# design.net
KiCad netlist of a schematic drawn in Altium Designer
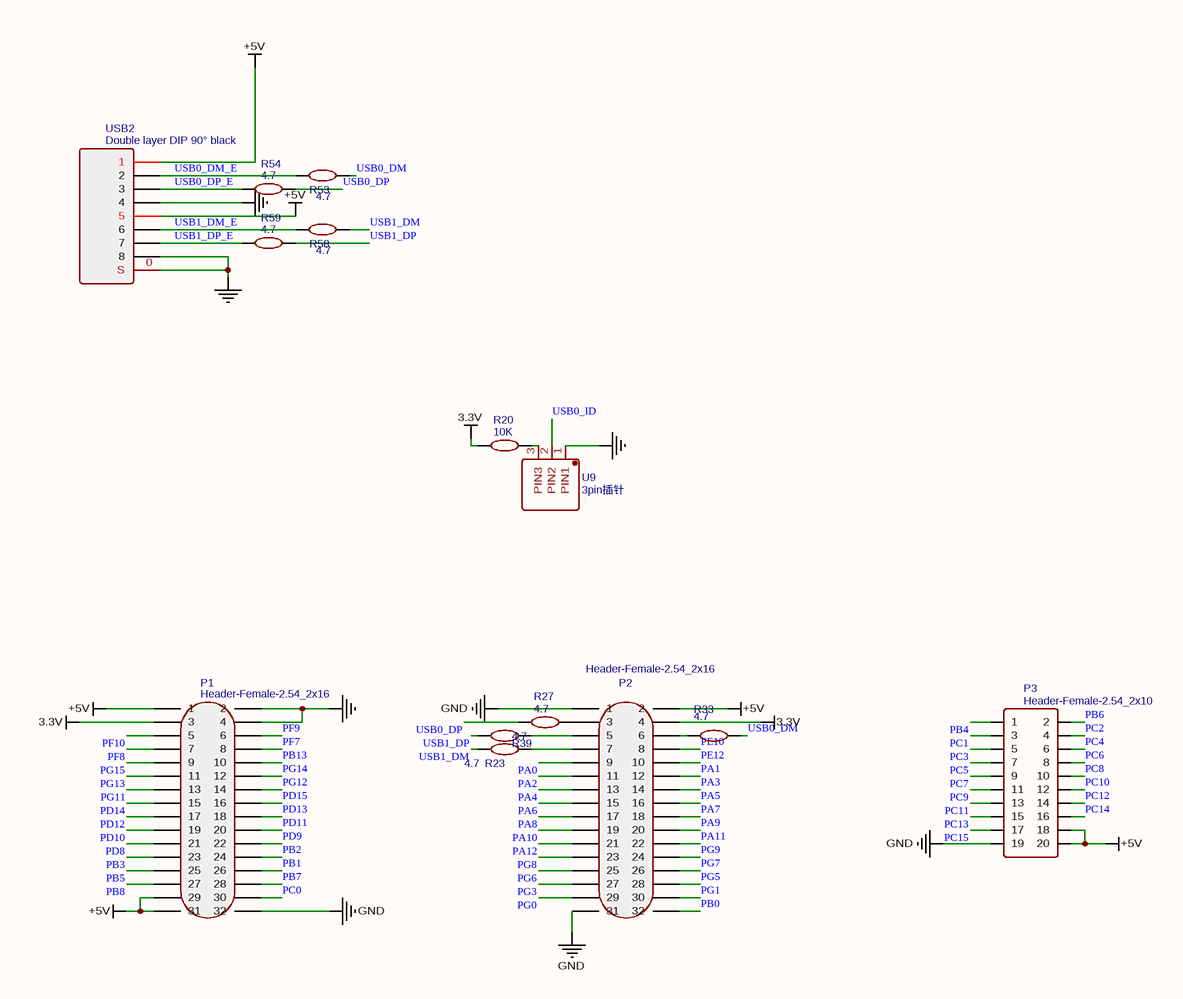
[diagram p0: 接口单元.schdoc]

(export (version "E")
  (design (tool "Eeschema 10.0.6"))
  (components
    (comp (ref "P1")
      (value "Header-Female-2.54_2x16")
      (footprint "HDR-16X2/2.54")
      (fields (field (name "BOM_SUPPLIER PART") "E55795"))
      (libsource (lib "altium-import") (part "root_0_Header-Female-2.54_2x16_"))
    )
    (comp (ref "P2")
      (value "Header-Female-2.54_2x16")
      (footprint "HDR-16X2/2.54")
      (fields (field (name "BOM_SUPPLIER PART") "E55795"))
      (libsource (lib "altium-import") (part "root_0_Header-Female-2.54_2x16_"))
    )
    (comp (ref "P3")
      (value "Header-Female-2.54_2x10")
      (footprint "HDR-10X2/2.54")
      (fields
        (field (name "BOM_MANUFACTURER PART") "2.54mm,2×10Double row female")
        (field (name "BOM_SUPPLIER PART") "C30867")
      )
      (libsource (lib "altium-import") (part "root_0_Header-Female-2.54_2x10_"))
    )
    (comp (ref "R20")
      (value "10K")
      (footprint "0603")
      (fields
        (field (name "BOM_MANUFACTURER PART") "0603WAF1002T5E")
        (field (name "BOM_SUPPLIER PART") "C25804")
      )
      (libsource (lib "altium-import") (part "root_2_10K_"))
    )
    (comp (ref "R23")
      (value "4.7")
      (footprint "0603")
      (fields
        (field (name "BOM_MANUFACTURER PART") "0603WAF470KT5E")
        (field (name "BOM_SUPPLIER PART") "C23164")
      )
      (libsource (lib "altium-import") (part "root_0_4.7_"))
    )
    (comp (ref "R27")
      (value "4.7")
      (footprint "0603")
      (fields
        (field (name "BOM_MANUFACTURER PART") "0603WAF470KT5E")
        (field (name "BOM_SUPPLIER PART") "C23164")
      )
      (libsource (lib "altium-import") (part "root_2_4.7_"))
    )
    (comp (ref "R33")
      (value "4.7")
      (footprint "0603")
      (fields
        (field (name "BOM_MANUFACTURER PART") "0603WAF470KT5E")
        (field (name "BOM_SUPPLIER PART") "C23164")
      )
      (libsource (lib "altium-import") (part "root_0_4.7_"))
    )
    (comp (ref "R39")
      (value "4.7")
      (footprint "0603")
      (fields
        (field (name "BOM_MANUFACTURER PART") "0603WAF470KT5E")
        (field (name "BOM_SUPPLIER PART") "C23164")
      )
      (libsource (lib "altium-import") (part "root_0_4.7_"))
    )
    (comp (ref "R53")
      (value "4.7")
      (footprint "0603")
      (fields
        (field (name "BOM_MANUFACTURER PART") "0603WAF470KT5E")
        (field (name "BOM_SUPPLIER PART") "C23164")
      )
      (libsource (lib "altium-import") (part "root_0_4.7_"))
    )
    (comp (ref "R54")
      (value "4.7")
      (footprint "0603")
      (fields
        (field (name "BOM_MANUFACTURER PART") "0603WAF470KT5E")
        (field (name "BOM_SUPPLIER PART") "C23164")
      )
      (libsource (lib "altium-import") (part "root_0_4.7_"))
    )
    (comp (ref "R58")
      (value "4.7")
      (footprint "0603")
      (fields
        (field (name "BOM_MANUFACTURER PART") "0603WAF470KT5E")
        (field (name "BOM_SUPPLIER PART") "C23164")
      )
      (libsource (lib "altium-import") (part "root_0_4.7_"))
    )
    (comp (ref "R59")
      (value "4.7")
      (footprint "0603")
      (fields
        (field (name "BOM_MANUFACTURER PART") "0603WAF470KT5E")
        (field (name "BOM_SUPPLIER PART") "C23164")
      )
      (libsource (lib "altium-import") (part "root_0_4.7_"))
    )
    (comp (ref "U9")
      (value "3pin插针")
      (footprint "HDR-3X1/2.54")
      (fields (field (name "CONTRIBUTOR") "DesignMyself"))
      (libsource (lib "altium-import") (part "root_3_3pin插针_"))
    )
    (comp (ref "USB2")
      (value "Double layer DIP 90° black")
      (footprint "USB-M-51")
      (fields (field (name "BOM_SUPPLIER PART") "C12049"))
      (libsource (lib "altium-import") (part "root_0_Double layer DIP 90° black_"))
    )
  )
  (nets
    (net (code "1") (name "+5V") (class "Default")
      (node (ref "P1") (pin "1") (pinfunction "1_1") (pintype "passive"))
      (node (ref "P1") (pin "29") (pinfunction "29_29") (pintype "passive"))
      (node (ref "P1") (pin "31") (pinfunction "31_31") (pintype "passive"))
      (node (ref "P2") (pin "2") (pinfunction "2_2") (pintype "passive"))
      (node (ref "P3") (pin "18") (pinfunction "18_18") (pintype "passive"))
      (node (ref "P3") (pin "20") (pinfunction "20_20") (pintype "passive"))
      (node (ref "USB2") (pin "1") (pinfunction "1_1") (pintype "passive"))
      (node (ref "USB2") (pin "5") (pinfunction "5_5") (pintype "passive"))
    )
    (net (code "2") (name "/PA0") (class "Default")
      (node (ref "P2") (pin "9") (pinfunction "9_9") (pintype "passive"))
    )
    (net (code "3") (name "/PA1") (class "Default")
      (node (ref "P2") (pin "12") (pinfunction "12_12") (pintype "passive"))
    )
    (net (code "4") (name "/PA2") (class "Default")
      (node (ref "P2") (pin "11") (pinfunction "11_11") (pintype "passive"))
    )
    (net (code "5") (name "/PA3") (class "Default")
      (node (ref "P2") (pin "14") (pinfunction "14_14") (pintype "passive"))
    )
    (net (code "6") (name "/PA4") (class "Default")
      (node (ref "P2") (pin "13") (pinfunction "13_13") (pintype "passive"))
    )
    (net (code "7") (name "/PA5") (class "Default")
      (node (ref "P2") (pin "16") (pinfunction "16_16") (pintype "passive"))
    )
    (net (code "8") (name "/PA6") (class "Default")
      (node (ref "P2") (pin "15") (pinfunction "15_15") (pintype "passive"))
    )
    (net (code "9") (name "/PA7") (class "Default")
      (node (ref "P2") (pin "18") (pinfunction "18_18") (pintype "passive"))
    )
    (net (code "10") (name "/PA8") (class "Default")
      (node (ref "P2") (pin "17") (pinfunction "17_17") (pintype "passive"))
    )
    (net (code "11") (name "/PA9") (class "Default")
      (node (ref "P2") (pin "20") (pinfunction "20_20") (pintype "passive"))
    )
    (net (code "12") (name "/PA10") (class "Default")
      (node (ref "P2") (pin "19") (pinfunction "19_19") (pintype "passive"))
    )
    (net (code "13") (name "/PA11") (class "Default")
      (node (ref "P2") (pin "22") (pinfunction "22_22") (pintype "passive"))
    )
    (net (code "14") (name "/PA12") (class "Default")
      (node (ref "P2") (pin "21") (pinfunction "21_21") (pintype "passive"))
    )
    (net (code "15") (name "/PB0") (class "Default")
      (node (ref "P2") (pin "32") (pinfunction "32_32") (pintype "passive"))
    )
    (net (code "16") (name "/PB1") (class "Default")
      (node (ref "P1") (pin "26") (pinfunction "26_26") (pintype "passive"))
    )
    (net (code "17") (name "/PB2") (class "Default")
      (node (ref "P1") (pin "24") (pinfunction "24_24") (pintype "passive"))
    )
    (net (code "18") (name "/PB3") (class "Default")
      (node (ref "P1") (pin "23") (pinfunction "23_23") (pintype "passive"))
    )
    (net (code "19") (name "/PB4") (class "Default")
      (node (ref "P3") (pin "1") (pinfunction "1_1") (pintype "passive"))
    )
    (net (code "20") (name "/PB5") (class "Default")
      (node (ref "P1") (pin "25") (pinfunction "25_25") (pintype "passive"))
    )
    (net (code "21") (name "/PB6") (class "Default")
      (node (ref "P3") (pin "2") (pinfunction "2_2") (pintype "passive"))
    )
    (net (code "22") (name "/PB7") (class "Default")
      (node (ref "P1") (pin "28") (pinfunction "28_28") (pintype "passive"))
    )
    (net (code "23") (name "/PB8") (class "Default")
      (node (ref "P1") (pin "27") (pinfunction "27_27") (pintype "passive"))
    )
    (net (code "24") (name "/PB13") (class "Default")
      (node (ref "P1") (pin "10") (pinfunction "10_10") (pintype "passive"))
    )
    (net (code "25") (name "/PC0") (class "Default")
      (node (ref "P1") (pin "30") (pinfunction "30_30") (pintype "passive"))
    )
    (net (code "26") (name "/PC1") (class "Default")
      (node (ref "P3") (pin "3") (pinfunction "3_3") (pintype "passive"))
    )
    (net (code "27") (name "/PC2") (class "Default")
      (node (ref "P3") (pin "4") (pinfunction "4_4") (pintype "passive"))
    )
    (net (code "28") (name "/PC3") (class "Default")
      (node (ref "P3") (pin "5") (pinfunction "5_5") (pintype "passive"))
    )
    (net (code "29") (name "/PC4") (class "Default")
      (node (ref "P3") (pin "6") (pinfunction "6_6") (pintype "passive"))
    )
    (net (code "30") (name "/PC5") (class "Default")
      (node (ref "P3") (pin "7") (pinfunction "7_7") (pintype "passive"))
    )
    (net (code "31") (name "/PC6") (class "Default")
      (node (ref "P3") (pin "8") (pinfunction "8_8") (pintype "passive"))
    )
    (net (code "32") (name "/PC7") (class "Default")
      (node (ref "P3") (pin "9") (pinfunction "9_9") (pintype "passive"))
    )
    (net (code "33") (name "/PC8") (class "Default")
      (node (ref "P3") (pin "10") (pinfunction "10_10") (pintype "passive"))
    )
    (net (code "34") (name "/PC9") (class "Default")
      (node (ref "P3") (pin "11") (pinfunction "11_11") (pintype "passive"))
    )
    (net (code "35") (name "/PC10") (class "Default")
      (node (ref "P3") (pin "12") (pinfunction "12_12") (pintype "passive"))
    )
    (net (code "36") (name "/PC11") (class "Default")
      (node (ref "P3") (pin "13") (pinfunction "13_13") (pintype "passive"))
    )
    (net (code "37") (name "/PC12") (class "Default")
      (node (ref "P3") (pin "14") (pinfunction "14_14") (pintype "passive"))
    )
    (net (code "38") (name "/PC13") (class "Default")
      (node (ref "P3") (pin "15") (pinfunction "15_15") (pintype "passive"))
    )
    (net (code "39") (name "/PC14") (class "Default")
      (node (ref "P3") (pin "16") (pinfunction "16_16") (pintype "passive"))
    )
    (net (code "40") (name "/PC15") (class "Default")
      (node (ref "P3") (pin "17") (pinfunction "17_17") (pintype "passive"))
    )
    (net (code "41") (name "/PD8") (class "Default")
      (node (ref "P1") (pin "21") (pinfunction "21_21") (pintype "passive"))
    )
    (net (code "42") (name "/PD9") (class "Default")
      (node (ref "P1") (pin "22") (pinfunction "22_22") (pintype "passive"))
    )
    (net (code "43") (name "/PD10") (class "Default")
      (node (ref "P1") (pin "19") (pinfunction "19_19") (pintype "passive"))
    )
    (net (code "44") (name "/PD11") (class "Default")
      (node (ref "P1") (pin "20") (pinfunction "20_20") (pintype "passive"))
    )
    (net (code "45") (name "/PD12") (class "Default")
      (node (ref "P1") (pin "17") (pinfunction "17_17") (pintype "passive"))
    )
    (net (code "46") (name "/PD13") (class "Default")
      (node (ref "P1") (pin "18") (pinfunction "18_18") (pintype "passive"))
    )
    (net (code "47") (name "/PD14") (class "Default")
      (node (ref "P1") (pin "15") (pinfunction "15_15") (pintype "passive"))
    )
    (net (code "48") (name "/PD15") (class "Default")
      (node (ref "P1") (pin "16") (pinfunction "16_16") (pintype "passive"))
    )
    (net (code "49") (name "/PE10") (class "Default")
      (node (ref "P2") (pin "8") (pinfunction "8_8") (pintype "passive"))
    )
    (net (code "50") (name "/PE12") (class "Default")
      (node (ref "P2") (pin "10") (pinfunction "10_10") (pintype "passive"))
    )
    (net (code "51") (name "/PF7") (class "Default")
      (node (ref "P1") (pin "8") (pinfunction "8_8") (pintype "passive"))
    )
    (net (code "52") (name "/PF8") (class "Default")
      (node (ref "P1") (pin "7") (pinfunction "7_7") (pintype "passive"))
    )
    (net (code "53") (name "/PF9") (class "Default")
      (node (ref "P1") (pin "6") (pinfunction "6_6") (pintype "passive"))
    )
    (net (code "54") (name "/PF10") (class "Default")
      (node (ref "P1") (pin "5") (pinfunction "5_5") (pintype "passive"))
    )
    (net (code "55") (name "/PG0") (class "Default")
      (node (ref "P2") (pin "29") (pinfunction "29_29") (pintype "passive"))
    )
    (net (code "56") (name "/PG1") (class "Default")
      (node (ref "P2") (pin "30") (pinfunction "30_30") (pintype "passive"))
    )
    (net (code "57") (name "/PG3") (class "Default")
      (node (ref "P2") (pin "27") (pinfunction "27_27") (pintype "passive"))
    )
    (net (code "58") (name "/PG5") (class "Default")
      (node (ref "P2") (pin "28") (pinfunction "28_28") (pintype "passive"))
    )
    (net (code "59") (name "/PG6") (class "Default")
      (node (ref "P2") (pin "25") (pinfunction "25_25") (pintype "passive"))
    )
    (net (code "60") (name "/PG7") (class "Default")
      (node (ref "P2") (pin "26") (pinfunction "26_26") (pintype "passive"))
    )
    (net (code "61") (name "/PG8") (class "Default")
      (node (ref "P2") (pin "23") (pinfunction "23_23") (pintype "passive"))
    )
    (net (code "62") (name "/PG9") (class "Default")
      (node (ref "P2") (pin "24") (pinfunction "24_24") (pintype "passive"))
    )
    (net (code "63") (name "/PG11") (class "Default")
      (node (ref "P1") (pin "13") (pinfunction "13_13") (pintype "passive"))
    )
    (net (code "64") (name "/PG12") (class "Default")
      (node (ref "P1") (pin "14") (pinfunction "14_14") (pintype "passive"))
    )
    (net (code "65") (name "/PG13") (class "Default")
      (node (ref "P1") (pin "11") (pinfunction "11_11") (pintype "passive"))
    )
    (net (code "66") (name "/PG14") (class "Default")
      (node (ref "P1") (pin "12") (pinfunction "12_12") (pintype "passive"))
    )
    (net (code "67") (name "/PG15") (class "Default")
      (node (ref "P1") (pin "9") (pinfunction "9_9") (pintype "passive"))
    )
    (net (code "68") (name "/USB0_DM") (class "Default")
      (node (ref "R33") (pin "2") (pinfunction "2_2") (pintype "passive"))
      (node (ref "R53") (pin "2") (pinfunction "2_2") (pintype "passive"))
    )
    (net (code "69") (name "/USB0_DM_E") (class "Default")
      (node (ref "R53") (pin "1") (pinfunction "1_1") (pintype "passive"))
      (node (ref "USB2") (pin "2") (pinfunction "2_2") (pintype "passive"))
    )
    (net (code "70") (name "/USB0_DP") (class "Default")
      (node (ref "R27") (pin "2") (pinfunction "2_2") (pintype "passive"))
      (node (ref "R54") (pin "2") (pinfunction "2_2") (pintype "passive"))
    )
    (net (code "71") (name "/USB0_DP_E") (class "Default")
      (node (ref "R54") (pin "1") (pinfunction "1_1") (pintype "passive"))
      (node (ref "USB2") (pin "3") (pinfunction "3_3") (pintype "passive"))
    )
    (net (code "72") (name "/USB0_ID") (class "Default")
      (node (ref "U9") (pin "2") (pinfunction "PIN2_2") (pintype "passive"))
    )
    (net (code "73") (name "/USB1_DM") (class "Default")
      (node (ref "R39") (pin "1") (pinfunction "1_1") (pintype "passive"))
      (node (ref "R58") (pin "2") (pinfunction "2_2") (pintype "passive"))
    )
    (net (code "74") (name "/USB1_DM_E") (class "Default")
      (node (ref "R58") (pin "1") (pinfunction "1_1") (pintype "passive"))
      (node (ref "USB2") (pin "6") (pinfunction "6_6") (pintype "passive"))
    )
    (net (code "75") (name "/USB1_DP") (class "Default")
      (node (ref "R23") (pin "1") (pinfunction "1_1") (pintype "passive"))
      (node (ref "R59") (pin "2") (pinfunction "2_2") (pintype "passive"))
    )
    (net (code "76") (name "/USB1_DP_E") (class "Default")
      (node (ref "R59") (pin "1") (pinfunction "1_1") (pintype "passive"))
      (node (ref "USB2") (pin "7") (pinfunction "7_7") (pintype "passive"))
    )
    (net (code "77") (name "3.3V") (class "Default")
      (node (ref "P1") (pin "3") (pinfunction "3_3") (pintype "passive"))
      (node (ref "P2") (pin "4") (pinfunction "4_4") (pintype "passive"))
      (node (ref "R20") (pin "2") (pinfunction "2_2") (pintype "passive"))
    )
    (net (code "78") (name "GND") (class "Default")
      (node (ref "P1") (pin "2") (pinfunction "2_2") (pintype "passive"))
      (node (ref "P1") (pin "32") (pinfunction "32_32") (pintype "passive"))
      (node (ref "P1") (pin "4") (pinfunction "4_4") (pintype "passive"))
      (node (ref "P2") (pin "1") (pinfunction "1_1") (pintype "passive"))
      (node (ref "P2") (pin "31") (pinfunction "31_31") (pintype "passive"))
      (node (ref "P3") (pin "19") (pinfunction "19_19") (pintype "passive"))
      (node (ref "U9") (pin "1") (pinfunction "PIN1_1") (pintype "passive"))
      (node (ref "USB2") (pin "0") (pinfunction "S_0") (pintype "passive"))
      (node (ref "USB2") (pin "4") (pinfunction "4_4") (pintype "passive"))
      (node (ref "USB2") (pin "8") (pinfunction "8_8") (pintype "passive"))
    )
    (net (code "79") (name "Net-(P2-Pad3)") (class "Default")
      (node (ref "P2") (pin "3") (pinfunction "3_3") (pintype "passive"))
      (node (ref "R27") (pin "1") (pinfunction "1_1") (pintype "passive"))
    )
    (net (code "80") (name "Net-(P2-Pad5)") (class "Default")
      (node (ref "P2") (pin "5") (pinfunction "5_5") (pintype "passive"))
      (node (ref "R23") (pin "2") (pinfunction "2_2") (pintype "passive"))
    )
    (net (code "81") (name "Net-(P2-Pad6)") (class "Default")
      (node (ref "P2") (pin "6") (pinfunction "6_6") (pintype "passive"))
      (node (ref "R33") (pin "1") (pinfunction "1_1") (pintype "passive"))
    )
    (net (code "82") (name "Net-(P2-Pad7)") (class "Default")
      (node (ref "P2") (pin "7") (pinfunction "7_7") (pintype "passive"))
      (node (ref "R39") (pin "2") (pinfunction "2_2") (pintype "passive"))
    )
    (net (code "83") (name "Net-(U9-PIN3)") (class "Default")
      (node (ref "R20") (pin "1") (pinfunction "1_1") (pintype "passive"))
      (node (ref "U9") (pin "3") (pinfunction "PIN3_3") (pintype "passive"))
    )
  )
)
